# simple-loop-active1b.net
KiCad netlist of a schematic drawn in EAGLE
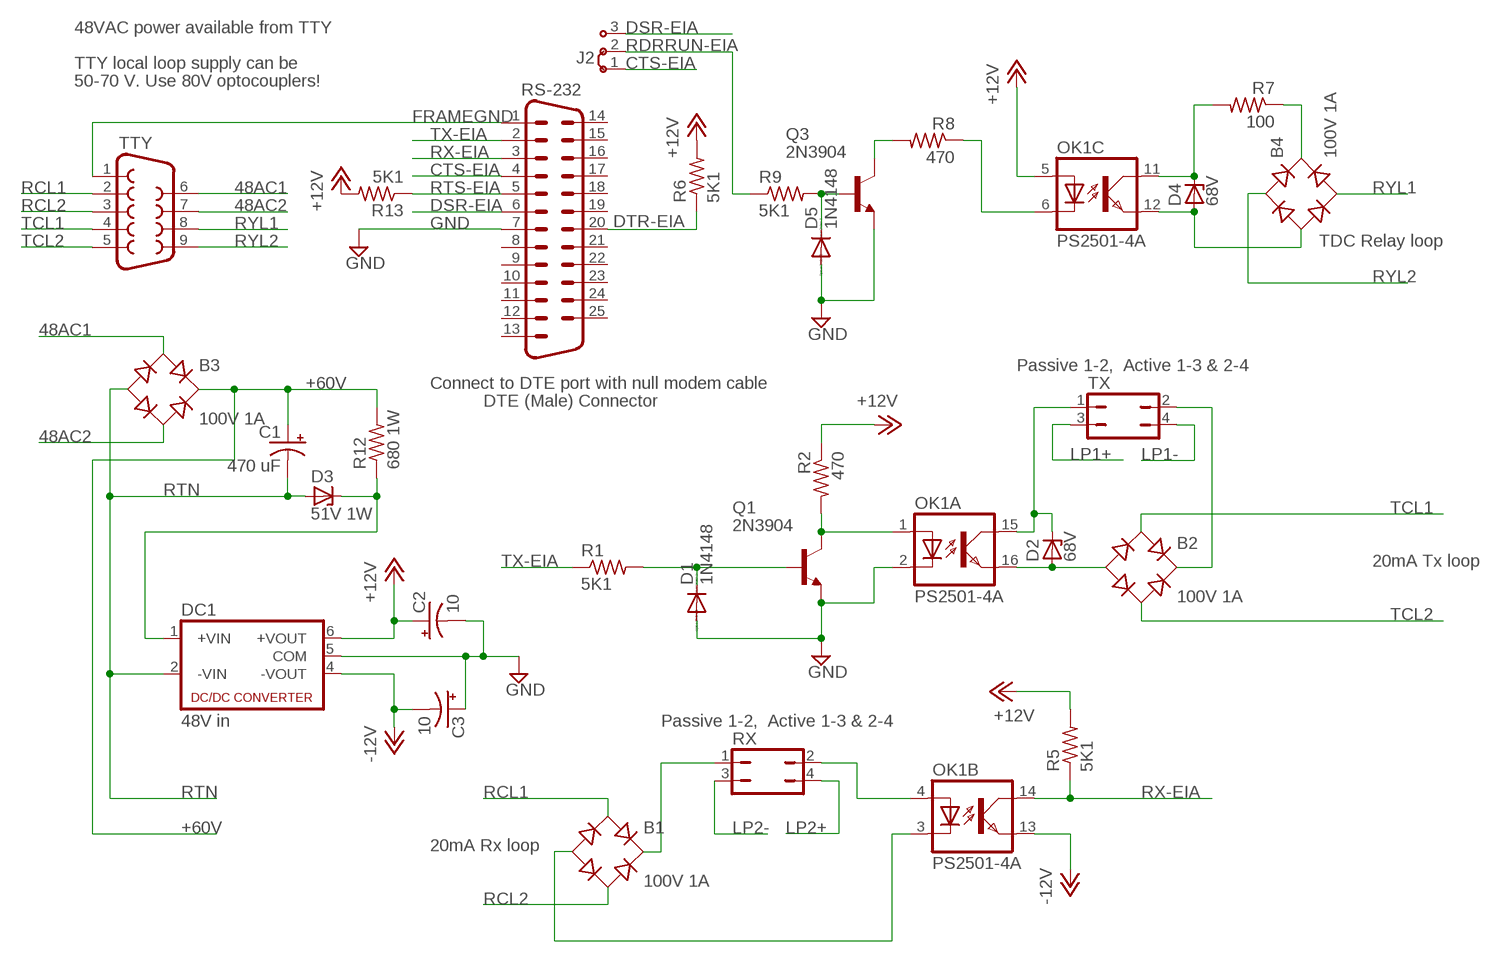
[diagram p0: schematic, sheet 1]
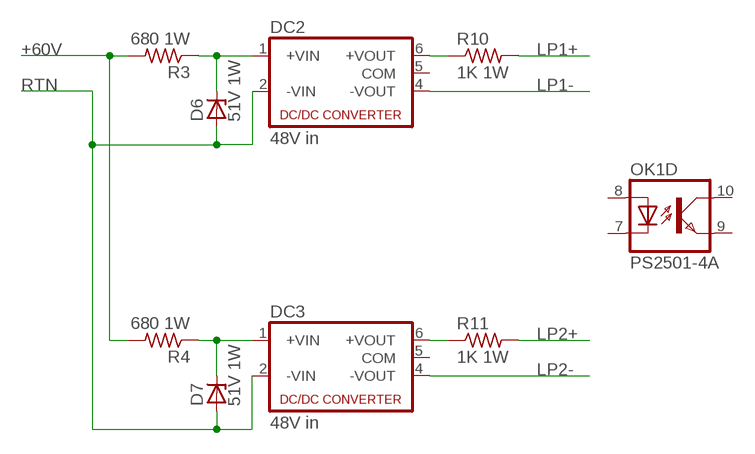
[diagram p1: schematic, sheet 2]

(export (version "E")
  (design (tool "Eeschema 10.0.6"))
  (components
    (comp (ref "B1")
      (value "100V 1A")
      (footprint "eagle-import:RB1A")
      (libsource (lib "eagle-import") (part "RB1A"))
    )
    (comp (ref "B2")
      (value "100V 1A")
      (footprint "eagle-import:RB1A")
      (libsource (lib "eagle-import") (part "RB1A"))
    )
    (comp (ref "B3")
      (value "100V 1A")
      (footprint "eagle-import:RB1A")
      (libsource (lib "eagle-import") (part "RB1A"))
    )
    (comp (ref "B4")
      (value "100V 1A")
      (footprint "eagle-import:RB1A")
      (libsource (lib "eagle-import") (part "RB1A"))
    )
    (comp (ref "C1")
      (value "470 uF")
      (footprint "eagle-import:E7,5-18")
      (libsource (lib "eagle-import") (part "CPOL-USE7.5-18"))
    )
    (comp (ref "C2")
      (value "10")
      (footprint "eagle-import:B45181A")
      (libsource (lib "eagle-import") (part "CPOL-USB45181A"))
    )
    (comp (ref "C3")
      (value "10")
      (footprint "eagle-import:B45181A")
      (libsource (lib "eagle-import") (part "CPOL-USB45181A"))
    )
    (comp (ref "D1")
      (value "1N4148")
      (footprint "eagle-import:DO35-10")
      (libsource (lib "eagle-import") (part "1N4148DO35-10"))
    )
    (comp (ref "D2")
      (value "68V")
      (footprint "eagle-import:DO41Z10")
      (libsource (lib "eagle-import") (part "ZENER-DIODEDO41Z10"))
    )
    (comp (ref "D3")
      (value "51V 1W")
      (footprint "eagle-import:DO41Z10")
      (libsource (lib "eagle-import") (part "ZENER-DIODEDO41Z10"))
    )
    (comp (ref "D4")
      (value "68V")
      (footprint "eagle-import:DO41Z10")
      (libsource (lib "eagle-import") (part "ZENER-DIODEDO41Z10"))
    )
    (comp (ref "D5")
      (value "1N4148")
      (footprint "eagle-import:DO35-10")
      (libsource (lib "eagle-import") (part "1N4148DO35-10"))
    )
    (comp (ref "DC1")
      (value "48V in")
      (footprint "eagle-import:NMA")
      (fields (field (name "MF") "C & D TECHNOLOGIES, INC") (field (name "MPN") "NMA0515SC"))
      (libsource (lib "eagle-import") (part "NMA"))
    )
    (comp (ref "J2")
      (value "J2X5MM")
      (footprint "eagle-import:05C")
      (libsource (lib "eagle-import") (part "J2X5MM"))
    )
    (comp (ref "OK1")
      (value "PS2501-4A")
      (footprint "eagle-import:DIL16")
      (fields (field (name "MF") "VISHAY/TELEFUNKEN") (field (name "MPN") "ILQ1"))
      (libsource (lib "eagle-import") (part "ILQ1"))
    )
    (comp (ref "Q1")
      (value "2N3904")
      (footprint "eagle-import:TO92")
      (libsource (lib "eagle-import") (part "2N3904"))
    )
    (comp (ref "Q3")
      (value "2N3904")
      (footprint "eagle-import:TO92")
      (libsource (lib "eagle-import") (part "2N3904"))
    )
    (comp (ref "R1")
      (value "5K1")
      (footprint "eagle-import:0207_10")
      (libsource (lib "eagle-import") (part "R-US_0207/10"))
    )
    (comp (ref "R2")
      (value "470")
      (footprint "eagle-import:0207_10")
      (libsource (lib "eagle-import") (part "R-US_0207/10"))
    )
    (comp (ref "R5")
      (value "5K1")
      (footprint "eagle-import:0207_10")
      (libsource (lib "eagle-import") (part "R-US_0207/10"))
    )
    (comp (ref "R6")
      (value "5K1")
      (footprint "eagle-import:0207_10")
      (libsource (lib "eagle-import") (part "R-US_0207/10"))
    )
    (comp (ref "R7")
      (value "100")
      (footprint "eagle-import:0207_10")
      (libsource (lib "eagle-import") (part "R-US_0207/10"))
    )
    (comp (ref "R8")
      (value "470")
      (footprint "eagle-import:0207_10")
      (libsource (lib "eagle-import") (part "R-US_0207/10"))
    )
    (comp (ref "R9")
      (value "5K1")
      (footprint "eagle-import:0207_10")
      (libsource (lib "eagle-import") (part "R-US_0207/10"))
    )
    (comp (ref "R12")
      (value "680 1W")
      (footprint "eagle-import:P0817V")
      (libsource (lib "eagle-import") (part "R-US_0817/7V"))
    )
    (comp (ref "R13")
      (value "5K1")
      (footprint "eagle-import:0207_10")
      (libsource (lib "eagle-import") (part "R-US_0207/10"))
    )
    (comp (ref "RS-232")
      (value "M25H")
      (footprint "eagle-import:M25H")
      (libsource (lib "eagle-import") (part "M25H"))
    )
    (comp (ref "RX")
      (value "JP2Q")
      (footprint "eagle-import:JP2Q")
      (libsource (lib "eagle-import") (part "JP2Q"))
    )
    (comp (ref "TTY")
      (value "F09H")
      (footprint "eagle-import:F09H")
      (libsource (lib "eagle-import") (part "F09H"))
    )
    (comp (ref "TX")
      (value "JP2Q")
      (footprint "eagle-import:JP2Q")
      (libsource (lib "eagle-import") (part "JP2Q"))
    )
    (comp (ref "D6")
      (value "51V 1W")
      (footprint "eagle-import:DO41Z10")
      (libsource (lib "eagle-import") (part "ZENER-DIODEDO41Z10"))
    )
    (comp (ref "D7")
      (value "51V 1W")
      (footprint "eagle-import:DO41Z10")
      (libsource (lib "eagle-import") (part "ZENER-DIODEDO41Z10"))
    )
    (comp (ref "DC2")
      (value "48V in")
      (footprint "eagle-import:NMA")
      (fields (field (name "MF") "C & D TECHNOLOGIES, INC") (field (name "MPN") "NMA0515SC"))
      (libsource (lib "eagle-import") (part "NMA"))
    )
    (comp (ref "DC3")
      (value "48V in")
      (footprint "eagle-import:NMA")
      (fields (field (name "MF") "C & D TECHNOLOGIES, INC") (field (name "MPN") "NMA0515SC"))
      (libsource (lib "eagle-import") (part "NMA"))
    )
    (comp (ref "R3")
      (value "680 1W")
      (footprint "eagle-import:P0817V")
      (libsource (lib "eagle-import") (part "R-US_0817/7V"))
    )
    (comp (ref "R4")
      (value "680 1W")
      (footprint "eagle-import:P0817V")
      (libsource (lib "eagle-import") (part "R-US_0817/7V"))
    )
    (comp (ref "R10")
      (value "1K 1W")
      (footprint "eagle-import:P0817V")
      (libsource (lib "eagle-import") (part "R-US_0817/7V"))
    )
    (comp (ref "R11")
      (value "1K 1W")
      (footprint "eagle-import:P0817V")
      (libsource (lib "eagle-import") (part "R-US_0817/7V"))
    )
  )
  (nets
    (net (code "1") (name "+12V") (class "Default")
      (node (ref "C2") (pin "+") (pinfunction "+_+") (pintype "passive"))
      (node (ref "DC1") (pin "6") (pinfunction "+VOUT_6") (pintype "passive"))
      (node (ref "OK1") (pin "5") (pinfunction "A_5") (pintype "passive"))
      (node (ref "R13") (pin "2") (pinfunction "2_2") (pintype "passive"))
      (node (ref "R2") (pin "1") (pinfunction "1_1") (pintype "passive"))
      (node (ref "R5") (pin "2") (pinfunction "2_2") (pintype "passive"))
      (node (ref "R6") (pin "2") (pinfunction "2_2") (pintype "passive"))
    )
    (net (code "2") (name "+60V") (class "Default")
      (node (ref "B3") (pin "+") (pinfunction "+_+") (pintype "passive"))
      (node (ref "C1") (pin "+") (pinfunction "+_+") (pintype "passive"))
      (node (ref "R12") (pin "2") (pinfunction "2_2") (pintype "passive"))
      (node (ref "R3") (pin "2") (pinfunction "2_2") (pintype "passive"))
      (node (ref "R4") (pin "2") (pinfunction "2_2") (pintype "passive"))
    )
    (net (code "3") (name "-12V") (class "Default")
      (node (ref "C3") (pin "-") (pinfunction "-_-") (pintype "passive"))
      (node (ref "DC1") (pin "4") (pinfunction "-VOUT_4") (pintype "passive"))
      (node (ref "OK1") (pin "13") (pinfunction "EMIT_13") (pintype "passive"))
    )
    (net (code "4") (name "48AC1") (class "Default")
      (node (ref "B3") (pin "AC1") (pinfunction "AC1_AC1") (pintype "passive"))
      (node (ref "TTY") (pin "6") (pinfunction "6_6") (pintype "passive"))
    )
    (net (code "5") (name "48AC2") (class "Default")
      (node (ref "B3") (pin "AC2") (pinfunction "AC2_AC2") (pintype "passive"))
      (node (ref "TTY") (pin "7") (pinfunction "7_7") (pintype "passive"))
    )
    (net (code "6") (name "CTS-EIA") (class "Default")
      (node (ref "J2") (pin "1") (pinfunction "1_1") (pintype "passive"))
      (node (ref "RS-232") (pin "4") (pinfunction "4_4") (pintype "passive"))
    )
    (net (code "7") (name "DSR-EIA") (class "Default")
      (node (ref "J2") (pin "3") (pinfunction "3_3") (pintype "passive"))
      (node (ref "RS-232") (pin "6") (pinfunction "6_6") (pintype "passive"))
    )
    (net (code "8") (name "DTR-EIA") (class "Default")
      (node (ref "R6") (pin "1") (pinfunction "1_1") (pintype "passive"))
      (node (ref "RS-232") (pin "20") (pinfunction "20_20") (pintype "passive"))
    )
    (net (code "9") (name "FRAMEGND") (class "Default")
      (node (ref "RS-232") (pin "1") (pinfunction "1_1") (pintype "passive"))
      (node (ref "TTY") (pin "1") (pinfunction "1_1") (pintype "passive"))
    )
    (net (code "10") (name "GND") (class "Default")
      (node (ref "C2") (pin "-") (pinfunction "-_-") (pintype "passive"))
      (node (ref "C3") (pin "+") (pinfunction "+_+") (pintype "passive"))
      (node (ref "D1") (pin "A") (pinfunction "A_A") (pintype "passive"))
      (node (ref "D5") (pin "A") (pinfunction "A_A") (pintype "passive"))
      (node (ref "DC1") (pin "5") (pinfunction "COM_5") (pintype "passive"))
      (node (ref "OK1") (pin "2") (pinfunction "C_2") (pintype "passive"))
      (node (ref "Q1") (pin "3") (pinfunction "E_3") (pintype "passive"))
      (node (ref "Q3") (pin "3") (pinfunction "E_3") (pintype "passive"))
      (node (ref "RS-232") (pin "7") (pinfunction "7_7") (pintype "passive"))
    )
    (net (code "11") (name "LP1+") (class "Default")
      (node (ref "R10") (pin "2") (pinfunction "2_2") (pintype "passive"))
      (node (ref "TX") (pin "3") (pinfunction "3_3") (pintype "passive"))
    )
    (net (code "12") (name "LP1-") (class "Default")
      (node (ref "DC2") (pin "4") (pinfunction "-VOUT_4") (pintype "passive"))
      (node (ref "TX") (pin "4") (pinfunction "4_4") (pintype "passive"))
    )
    (net (code "13") (name "LP2+") (class "Default")
      (node (ref "R11") (pin "2") (pinfunction "2_2") (pintype "passive"))
      (node (ref "RX") (pin "4") (pinfunction "4_4") (pintype "passive"))
    )
    (net (code "14") (name "LP2-") (class "Default")
      (node (ref "DC3") (pin "4") (pinfunction "-VOUT_4") (pintype "passive"))
      (node (ref "RX") (pin "3") (pinfunction "3_3") (pintype "passive"))
    )
    (net (code "15") (name "Net-(B1-Pad+)") (class "Default")
      (node (ref "B1") (pin "+") (pinfunction "+_+") (pintype "passive"))
      (node (ref "RX") (pin "1") (pinfunction "1_1") (pintype "passive"))
    )
    (net (code "16") (name "Net-(B2-Pad+)") (class "Default")
      (node (ref "B2") (pin "+") (pinfunction "+_+") (pintype "passive"))
      (node (ref "TX") (pin "2") (pinfunction "2_2") (pintype "passive"))
    )
    (net (code "17") (name "Net-(B4-Pad+)") (class "Default")
      (node (ref "B4") (pin "+") (pinfunction "+_+") (pintype "passive"))
      (node (ref "R7") (pin "1") (pinfunction "1_1") (pintype "passive"))
    )
    (net (code "18") (name "Net-(DC1-+VIN)") (class "Default")
      (node (ref "D3") (pin "C") (pinfunction "C_C") (pintype "passive"))
      (node (ref "DC1") (pin "1") (pinfunction "+VIN_1") (pintype "passive"))
      (node (ref "R12") (pin "1") (pinfunction "1_1") (pintype "passive"))
    )
    (net (code "19") (name "Net-(DC2-+VIN)") (class "Default")
      (node (ref "D6") (pin "C") (pinfunction "C_C") (pintype "passive"))
      (node (ref "DC2") (pin "1") (pinfunction "+VIN_1") (pintype "passive"))
      (node (ref "R3") (pin "1") (pinfunction "1_1") (pintype "passive"))
    )
    (net (code "20") (name "Net-(DC2-+VOUT)") (class "Default")
      (node (ref "DC2") (pin "6") (pinfunction "+VOUT_6") (pintype "passive"))
      (node (ref "R10") (pin "1") (pinfunction "1_1") (pintype "passive"))
    )
    (net (code "21") (name "Net-(DC3-+VIN)") (class "Default")
      (node (ref "D7") (pin "C") (pinfunction "C_C") (pintype "passive"))
      (node (ref "DC3") (pin "1") (pinfunction "+VIN_1") (pintype "passive"))
      (node (ref "R4") (pin "1") (pinfunction "1_1") (pintype "passive"))
    )
    (net (code "22") (name "Net-(DC3-+VOUT)") (class "Default")
      (node (ref "DC3") (pin "6") (pinfunction "+VOUT_6") (pintype "passive"))
      (node (ref "R11") (pin "1") (pinfunction "1_1") (pintype "passive"))
    )
    (net (code "23") (name "Net-(OK1A-A)") (class "Default")
      (node (ref "OK1") (pin "1") (pinfunction "A_1") (pintype "passive"))
      (node (ref "Q1") (pin "1") (pinfunction "C_1") (pintype "passive"))
      (node (ref "R2") (pin "2") (pinfunction "2_2") (pintype "passive"))
    )
    (net (code "24") (name "Net-(OK1A-COL)") (class "Default")
      (node (ref "D2") (pin "C") (pinfunction "C_C") (pintype "passive"))
      (node (ref "OK1") (pin "15") (pinfunction "COL_15") (pintype "passive"))
      (node (ref "TX") (pin "1") (pinfunction "1_1") (pintype "passive"))
    )
    (net (code "25") (name "Net-(OK1A-EMIT)") (class "Default")
      (node (ref "B2") (pin "-") (pinfunction "-_-") (pintype "passive"))
      (node (ref "D2") (pin "A") (pinfunction "A_A") (pintype "passive"))
      (node (ref "OK1") (pin "16") (pinfunction "EMIT_16") (pintype "passive"))
    )
    (net (code "26") (name "Net-(OK1B-A)") (class "Default")
      (node (ref "OK1") (pin "4") (pinfunction "A_4") (pintype "passive"))
      (node (ref "RX") (pin "2") (pinfunction "2_2") (pintype "passive"))
    )
    (net (code "27") (name "Net-(OK1B-C)") (class "Default")
      (node (ref "B1") (pin "-") (pinfunction "-_-") (pintype "passive"))
      (node (ref "OK1") (pin "3") (pinfunction "C_3") (pintype "passive"))
    )
    (net (code "28") (name "Net-(OK1C-C)") (class "Default")
      (node (ref "OK1") (pin "6") (pinfunction "C_6") (pintype "passive"))
      (node (ref "R8") (pin "1") (pinfunction "1_1") (pintype "passive"))
    )
    (net (code "29") (name "Net-(OK1C-COL)") (class "Default")
      (node (ref "D4") (pin "C") (pinfunction "C_C") (pintype "passive"))
      (node (ref "OK1") (pin "11") (pinfunction "COL_11") (pintype "passive"))
      (node (ref "R7") (pin "2") (pinfunction "2_2") (pintype "passive"))
    )
    (net (code "30") (name "Net-(OK1C-EMIT)") (class "Default")
      (node (ref "B4") (pin "-") (pinfunction "-_-") (pintype "passive"))
      (node (ref "D4") (pin "A") (pinfunction "A_A") (pintype "passive"))
      (node (ref "OK1") (pin "12") (pinfunction "EMIT_12") (pintype "passive"))
    )
    (net (code "31") (name "Net-(Q1-B)") (class "Default")
      (node (ref "D1") (pin "C") (pinfunction "C_C") (pintype "passive"))
      (node (ref "Q1") (pin "2") (pinfunction "B_2") (pintype "passive"))
      (node (ref "R1") (pin "2") (pinfunction "2_2") (pintype "passive"))
    )
    (net (code "32") (name "Net-(Q3-B)") (class "Default")
      (node (ref "D5") (pin "C") (pinfunction "C_C") (pintype "passive"))
      (node (ref "Q3") (pin "2") (pinfunction "B_2") (pintype "passive"))
      (node (ref "R9") (pin "2") (pinfunction "2_2") (pintype "passive"))
    )
    (net (code "33") (name "Net-(Q3-C)") (class "Default")
      (node (ref "Q3") (pin "1") (pinfunction "C_1") (pintype "passive"))
      (node (ref "R8") (pin "2") (pinfunction "2_2") (pintype "passive"))
    )
    (net (code "34") (name "RCL1") (class "Default")
      (node (ref "B1") (pin "AC1") (pinfunction "AC1_AC1") (pintype "passive"))
      (node (ref "TTY") (pin "2") (pinfunction "2_2") (pintype "passive"))
    )
    (net (code "35") (name "RCL2") (class "Default")
      (node (ref "B1") (pin "AC2") (pinfunction "AC2_AC2") (pintype "passive"))
      (node (ref "TTY") (pin "3") (pinfunction "3_3") (pintype "passive"))
    )
    (net (code "36") (name "RDRRUN-EIA") (class "Default")
      (node (ref "J2") (pin "2") (pinfunction "2_2") (pintype "passive"))
      (node (ref "R9") (pin "1") (pinfunction "1_1") (pintype "passive"))
    )
    (net (code "37") (name "RTN") (class "Default")
      (node (ref "B3") (pin "-") (pinfunction "-_-") (pintype "passive"))
      (node (ref "C1") (pin "-") (pinfunction "-_-") (pintype "passive"))
      (node (ref "D3") (pin "A") (pinfunction "A_A") (pintype "passive"))
      (node (ref "D6") (pin "A") (pinfunction "A_A") (pintype "passive"))
      (node (ref "D7") (pin "A") (pinfunction "A_A") (pintype "passive"))
      (node (ref "DC1") (pin "2") (pinfunction "-VIN_2") (pintype "passive"))
      (node (ref "DC2") (pin "2") (pinfunction "-VIN_2") (pintype "passive"))
      (node (ref "DC3") (pin "2") (pinfunction "-VIN_2") (pintype "passive"))
    )
    (net (code "38") (name "RTS-EIA") (class "Default")
      (node (ref "R13") (pin "1") (pinfunction "1_1") (pintype "passive"))
      (node (ref "RS-232") (pin "5") (pinfunction "5_5") (pintype "passive"))
    )
    (net (code "39") (name "RX-EIA") (class "Default")
      (node (ref "OK1") (pin "14") (pinfunction "COL_14") (pintype "passive"))
      (node (ref "R5") (pin "1") (pinfunction "1_1") (pintype "passive"))
      (node (ref "RS-232") (pin "3") (pinfunction "3_3") (pintype "passive"))
    )
    (net (code "40") (name "RYL1") (class "Default")
      (node (ref "B4") (pin "AC2") (pinfunction "AC2_AC2") (pintype "passive"))
      (node (ref "TTY") (pin "8") (pinfunction "8_8") (pintype "passive"))
    )
    (net (code "41") (name "RYL2") (class "Default")
      (node (ref "B4") (pin "AC1") (pinfunction "AC1_AC1") (pintype "passive"))
      (node (ref "TTY") (pin "9") (pinfunction "9_9") (pintype "passive"))
    )
    (net (code "42") (name "TCL1") (class "Default")
      (node (ref "B2") (pin "AC1") (pinfunction "AC1_AC1") (pintype "passive"))
      (node (ref "TTY") (pin "4") (pinfunction "4_4") (pintype "passive"))
    )
    (net (code "43") (name "TCL2") (class "Default")
      (node (ref "B2") (pin "AC2") (pinfunction "AC2_AC2") (pintype "passive"))
      (node (ref "TTY") (pin "5") (pinfunction "5_5") (pintype "passive"))
    )
    (net (code "44") (name "TX-EIA") (class "Default")
      (node (ref "R1") (pin "1") (pinfunction "1_1") (pintype "passive"))
      (node (ref "RS-232") (pin "2") (pinfunction "2_2") (pintype "passive"))
    )
    (net (code "45") (name "unconnected-(DC2-COM-Pad5)") (class "Default")
      (node (ref "DC2") (pin "5") (pinfunction "COM_5") (pintype "passive"))
    )
    (net (code "46") (name "unconnected-(DC3-COM-Pad5)") (class "Default")
      (node (ref "DC3") (pin "5") (pinfunction "COM_5") (pintype "passive"))
    )
    (net (code "47") (name "unconnected-(OK1D-A-Pad8)") (class "Default")
      (node (ref "OK1") (pin "8") (pinfunction "A_8") (pintype "passive"))
    )
    (net (code "48") (name "unconnected-(OK1D-C-Pad7)") (class "Default")
      (node (ref "OK1") (pin "7") (pinfunction "C_7") (pintype "passive"))
    )
    (net (code "49") (name "unconnected-(OK1D-COL-Pad10)") (class "Default")
      (node (ref "OK1") (pin "10") (pinfunction "COL_10") (pintype "passive"))
    )
    (net (code "50") (name "unconnected-(OK1D-EMIT-Pad9)") (class "Default")
      (node (ref "OK1") (pin "9") (pinfunction "EMIT_9") (pintype "passive"))
    )
    (net (code "51") (name "unconnected-(RS-232-Pad8)") (class "Default")
      (node (ref "RS-232") (pin "8") (pinfunction "8_8") (pintype "passive"))
    )
    (net (code "52") (name "unconnected-(RS-232-Pad9)") (class "Default")
      (node (ref "RS-232") (pin "9") (pinfunction "9_9") (pintype "passive"))
    )
    (net (code "53") (name "unconnected-(RS-232-Pad10)") (class "Default")
      (node (ref "RS-232") (pin "10") (pinfunction "10_10") (pintype "passive"))
    )
    (net (code "54") (name "unconnected-(RS-232-Pad11)") (class "Default")
      (node (ref "RS-232") (pin "11") (pinfunction "11_11") (pintype "passive"))
    )
    (net (code "55") (name "unconnected-(RS-232-Pad12)") (class "Default")
      (node (ref "RS-232") (pin "12") (pinfunction "12_12") (pintype "passive"))
    )
    (net (code "56") (name "unconnected-(RS-232-Pad13)") (class "Default")
      (node (ref "RS-232") (pin "13") (pinfunction "13_13") (pintype "passive"))
    )
    (net (code "57") (name "unconnected-(RS-232-Pad14)") (class "Default")
      (node (ref "RS-232") (pin "14") (pinfunction "14_14") (pintype "passive"))
    )
    (net (code "58") (name "unconnected-(RS-232-Pad15)") (class "Default")
      (node (ref "RS-232") (pin "15") (pinfunction "15_15") (pintype "passive"))
    )
    (net (code "59") (name "unconnected-(RS-232-Pad16)") (class "Default")
      (node (ref "RS-232") (pin "16") (pinfunction "16_16") (pintype "passive"))
    )
    (net (code "60") (name "unconnected-(RS-232-Pad17)") (class "Default")
      (node (ref "RS-232") (pin "17") (pinfunction "17_17") (pintype "passive"))
    )
    (net (code "61") (name "unconnected-(RS-232-Pad18)") (class "Default")
      (node (ref "RS-232") (pin "18") (pinfunction "18_18") (pintype "passive"))
    )
    (net (code "62") (name "unconnected-(RS-232-Pad19)") (class "Default")
      (node (ref "RS-232") (pin "19") (pinfunction "19_19") (pintype "passive"))
    )
    (net (code "63") (name "unconnected-(RS-232-Pad21)") (class "Default")
      (node (ref "RS-232") (pin "21") (pinfunction "21_21") (pintype "passive"))
    )
    (net (code "64") (name "unconnected-(RS-232-Pad22)") (class "Default")
      (node (ref "RS-232") (pin "22") (pinfunction "22_22") (pintype "passive"))
    )
    (net (code "65") (name "unconnected-(RS-232-Pad23)") (class "Default")
      (node (ref "RS-232") (pin "23") (pinfunction "23_23") (pintype "passive"))
    )
    (net (code "66") (name "unconnected-(RS-232-Pad24)") (class "Default")
      (node (ref "RS-232") (pin "24") (pinfunction "24_24") (pintype "passive"))
    )
    (net (code "67") (name "unconnected-(RS-232-Pad25)") (class "Default")
      (node (ref "RS-232") (pin "25") (pinfunction "25_25") (pintype "passive"))
    )
  )
)
